# Host_reset_spno.net
KiCad netlist of a schematic drawn in Altium Designer
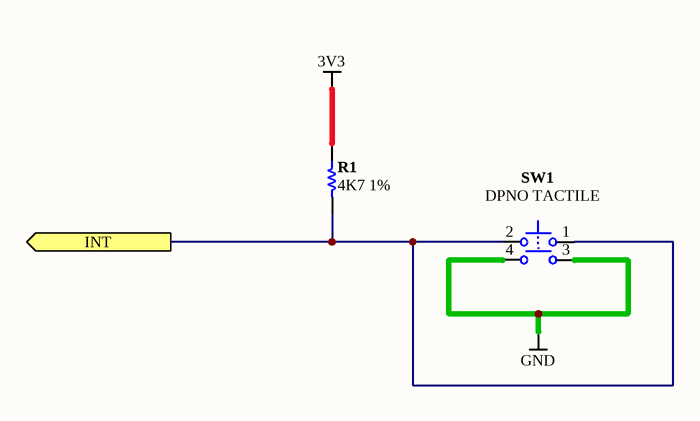
[diagram p0: Host_reset_spno.schdoc]

(export (version "E")
  (design (tool "Eeschema 10.0.6"))
  (components
    (comp (ref "R1")
      (value "4K7 1%")
      (footprint "RESC1005-STAR")
      (description "Resistor, 4K7 1% 0402 (1005)")
      (fields (field (name "TOLERANCE") "1 %"))
      (libsource (lib "altium-import") (part "root_0_mirrored_RES_"))
    )
    (comp (ref "SW1")
      (value "DPNO TACTILE")
      (footprint "IT-2175")
      (description "Switch, DPNO Push Button Through-Hole")
      (libsource (lib "AltiumDesignLibrary") (part "SWI-PB-DPNO"))
    )
  )
  (nets
    (net (code "1") (name "/INT") (class "Default")
      (node (ref "R1") (pin "2") (pinfunction "2_2") (pintype "passive"))
      (node (ref "SW1") (pin "1") (pinfunction "1_1") (pintype "passive"))
      (node (ref "SW1") (pin "2") (pinfunction "2_2") (pintype "passive"))
    )
    (net (code "2") (name "3V3") (class "Default")
      (node (ref "R1") (pin "1") (pinfunction "1_1") (pintype "passive"))
    )
    (net (code "3") (name "GND") (class "Default")
      (node (ref "SW1") (pin "3") (pinfunction "3_3") (pintype "passive"))
      (node (ref "SW1") (pin "4") (pinfunction "4_4") (pintype "passive"))
    )
  )
)
